# GSM_GPS.net
KiCad netlist of a schematic drawn in Altium Designer
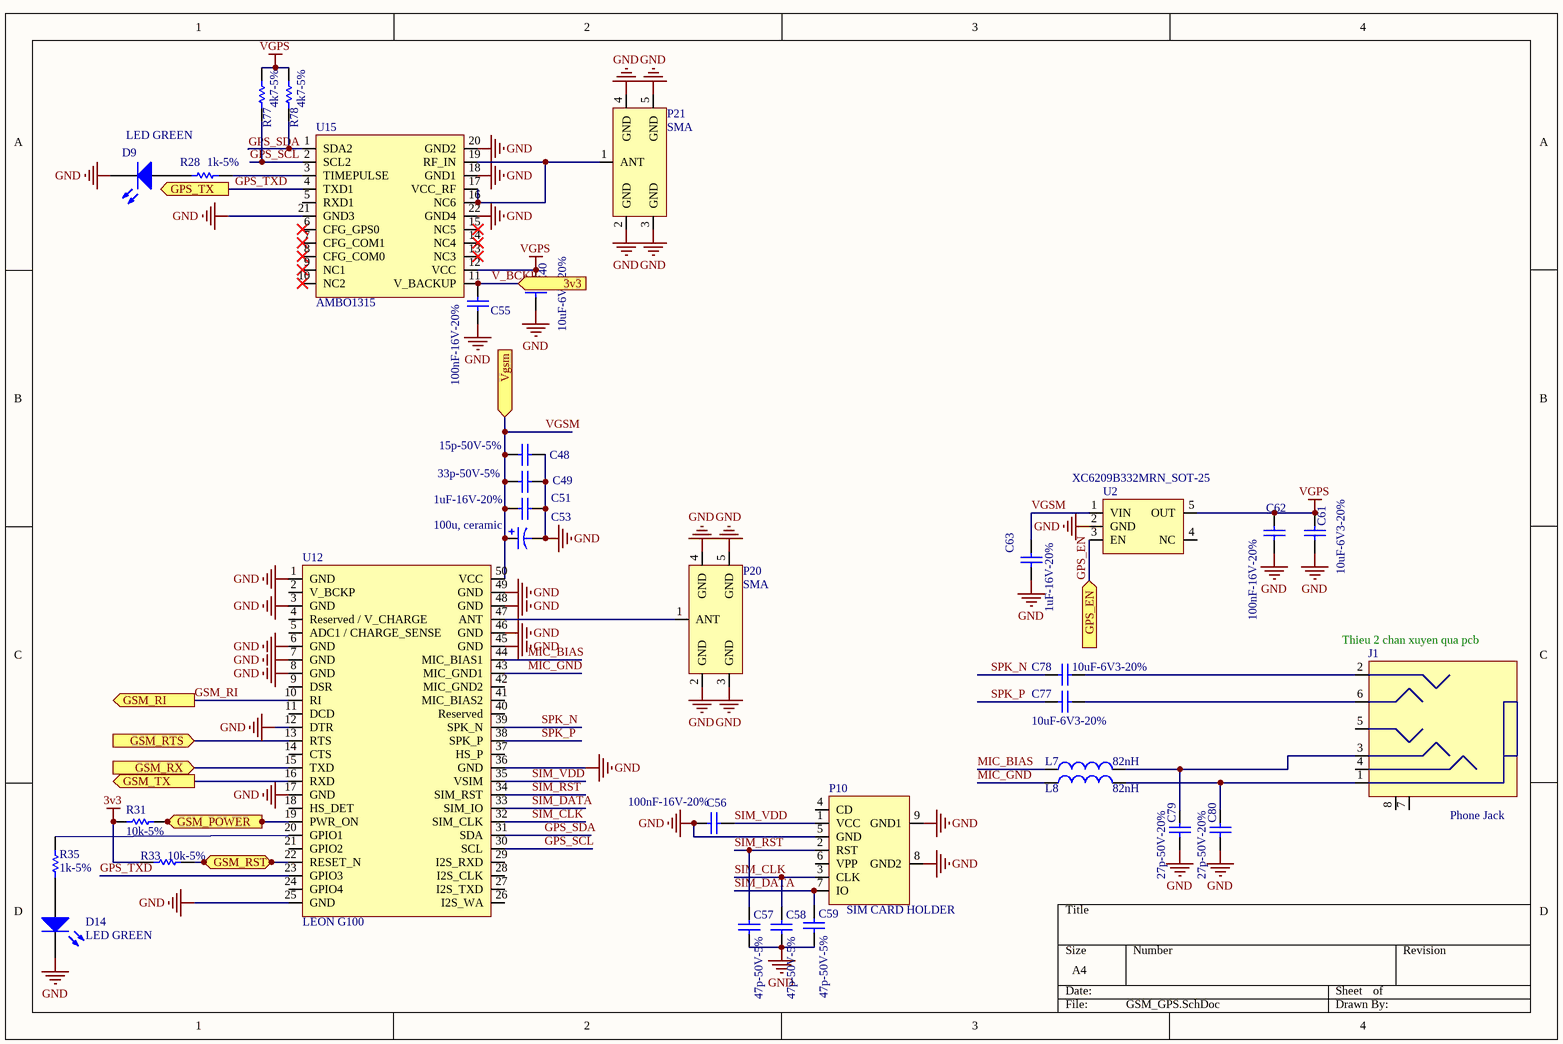
[diagram p0: GSM_GPS.SchDoc]

(export (version "E")
  (design (tool "Eeschema 10.0.6"))
  (components
    (comp (ref "C40")
      (value "10uF-6V3-20%")
      (footprint "C0603")
      (description "CAP CER 10UF 6.3V 20% X5R 0603")
      (fields
        (field (name "MANUFACTURER") "Murata Electronics North America")
        (field (name "DIGI-KEY PART NUMBER") "490-3896-1-ND")
        (field (name "PUBLISHER") "Altium Limited")
      )
      (libsource (lib "Miscellaneous Devices") (part "Cap"))
    )
    (comp (ref "C48")
      (value "15p-50V-5%")
      (footprint "C0402")
      (description "CAP CER 15PF 50V 5% NPO 0402")
      (fields
        (field (name "MANUFACTURER") "Yageo")
        (field (name "DIGI-KEY PART NUMBER") "311-1017-1-ND")
        (field (name "PUBLISHER") "Altium Limited")
      )
      (libsource (lib "Miscellaneous Devices") (part "Cap"))
    )
    (comp (ref "C49")
      (value "33p-50V-5%")
      (footprint "C0402")
      (description "CAP CER 33PF 50V 5% NPO 0402")
      (fields
        (field (name "MANUFACTURER") "Yageo")
        (field (name "DIGI-KEY PART NUMBER") "311-1020-1-ND")
        (field (name "PUBLISHER") "Altium Limited")
      )
      (libsource (lib "Miscellaneous Devices") (part "Cap"))
    )
    (comp (ref "C51")
      (value "1uF-16V-20%")
      (footprint "C0603")
      (description "CAP CER 1UF 16V Y5V 0603")
      (fields
        (field (name "MANUFACTURER") "Yageo")
        (field (name "DIGI-KEY PART NUMBER") "311-1372-1-ND")
        (field (name "PUBLISHER") "Altium Limited")
      )
      (libsource (lib "Miscellaneous Devices") (part "Cap"))
    )
    (comp (ref "C53")
      (value "100u, ceramic")
      (footprint "C1210")
      (description "CAP CER 100UF 10V 20% X5R 1812")
      (fields
        (field (name "DIGI-KEY PART NUMBER") "445-7743-2-ND")
        (field (name "MANUFACTURER PART NUMBER") "C4532X5R1A107M")
        (field (name "PUBLISHER") "Altium Limited")
      )
      (libsource (lib "Miscellaneous Devices") (part "Cap Pol3"))
    )
    (comp (ref "C55")
      (value "100nF-16V-20%")
      (footprint "C0402")
      (description "CAP CER 0.1UF 16V Y5V 0402")
      (fields
        (field (name "MANUFACTURER") "Yageo")
        (field (name "DIGI-KEY PART NUMBER") "311-1047-1-ND")
        (field (name "PUBLISHER") "Altium Limited")
      )
      (libsource (lib "Miscellaneous Devices") (part "Cap"))
    )
    (comp (ref "C56")
      (value "100nF-16V-20%")
      (footprint "C0402")
      (description "CAP CER 0.1UF 16V Y5V 0402")
      (fields
        (field (name "MANUFACTURER") "Yageo")
        (field (name "DIGI-KEY PART NUMBER") "311-1047-1-ND")
        (field (name "PUBLISHER") "Altium Limited")
      )
      (libsource (lib "Miscellaneous Devices") (part "Cap"))
    )
    (comp (ref "C57")
      (value "47p-50V-5%")
      (footprint "C0402")
      (description "CAP CER 47PF 50V 5% NPO 0402")
      (fields
        (field (name "MANUFACTURER") "Yageo")
        (field (name "DIGI-KEY PART NUMBER") "311-1021-1-ND")
        (field (name "PUBLISHER") "Altium Limited")
      )
      (libsource (lib "Miscellaneous Devices") (part "Cap"))
    )
    (comp (ref "C58")
      (value "47p-50V-5%")
      (footprint "C0402")
      (description "CAP CER 47PF 50V 5% NPO 0402")
      (fields
        (field (name "MANUFACTURER") "Yageo")
        (field (name "DIGI-KEY PART NUMBER") "311-1021-1-ND")
        (field (name "PUBLISHER") "Altium Limited")
      )
      (libsource (lib "Miscellaneous Devices") (part "Cap"))
    )
    (comp (ref "C59")
      (value "47p-50V-5%")
      (footprint "C0402")
      (description "CAP CER 47PF 50V 5% NPO 0402")
      (fields
        (field (name "MANUFACTURER") "Yageo")
        (field (name "DIGI-KEY PART NUMBER") "311-1021-1-ND")
        (field (name "PUBLISHER") "Altium Limited")
      )
      (libsource (lib "Miscellaneous Devices") (part "Cap"))
    )
    (comp (ref "C61")
      (value "10uF-6V3-20%")
      (footprint "C0603")
      (description "CAP CER 10UF 6.3V 20% X5R 0603")
      (fields
        (field (name "MANUFACTURER") "Murata Electronics North America")
        (field (name "DIGI-KEY PART NUMBER") "490-3896-1-ND")
        (field (name "PUBLISHER") "Altium Limited")
      )
      (libsource (lib "Miscellaneous Devices") (part "Cap"))
    )
    (comp (ref "C62")
      (value "100nF-16V-20%")
      (footprint "C0402")
      (description "CAP CER 0.1UF 16V Y5V 0402")
      (fields
        (field (name "MANUFACTURER") "Yageo")
        (field (name "DIGI-KEY PART NUMBER") "311-1047-1-ND")
        (field (name "PUBLISHER") "Altium Limited")
      )
      (libsource (lib "Miscellaneous Devices") (part "Cap"))
    )
    (comp (ref "C63")
      (value "1uF-16V-20%")
      (footprint "C0603")
      (description "CAP CER 1UF 16V Y5V 0603")
      (fields
        (field (name "MANUFACTURER") "Yageo")
        (field (name "DIGI-KEY PART NUMBER") "311-1372-1-ND")
        (field (name "PUBLISHER") "Altium Limited")
      )
      (libsource (lib "Miscellaneous Devices") (part "Cap"))
    )
    (comp (ref "C77")
      (value "10uF-6V3-20%")
      (footprint "C0603")
      (description "CAP CER 10UF 6.3V 20% X5R 0603")
      (fields
        (field (name "MANUFACTURER") "Murata Electronics North America")
        (field (name "DIGI-KEY PART NUMBER") "490-3896-1-ND")
        (field (name "PUBLISHER") "Altium Limited")
      )
      (libsource (lib "Miscellaneous Devices") (part "Cap"))
    )
    (comp (ref "C78")
      (value "10uF-6V3-20%")
      (footprint "C0603")
      (description "CAP CER 10UF 6.3V 20% X5R 0603")
      (fields
        (field (name "MANUFACTURER") "Murata Electronics North America")
        (field (name "DIGI-KEY PART NUMBER") "490-3896-1-ND")
        (field (name "PUBLISHER") "Altium Limited")
      )
      (libsource (lib "Miscellaneous Devices") (part "Cap"))
    )
    (comp (ref "C79")
      (value "27p-50V-20%")
      (footprint "C0402")
      (description "CAP CER 27PF 50V 5% NPO 0402")
      (fields
        (field (name "MANUFACTURER") "Murata Electronics North America")
        (field (name "DIGI-KEY PART NUMBER") "490-5869-1-ND")
        (field (name "PUBLISHER") "Altium Limited")
      )
      (libsource (lib "Miscellaneous Devices") (part "Cap"))
    )
    (comp (ref "C80")
      (value "27p-50V-20%")
      (footprint "C0402")
      (description "CAP CER 27PF 50V 5% NPO 0402")
      (fields
        (field (name "MANUFACTURER") "Murata Electronics North America")
        (field (name "DIGI-KEY PART NUMBER") "490-5869-1-ND")
        (field (name "PUBLISHER") "Altium Limited")
      )
      (libsource (lib "Miscellaneous Devices") (part "Cap"))
    )
    (comp (ref "D9")
      (value "LED GREEN")
      (footprint "LED0603-G")
      (description "LED GREEN CLEAR THIN 0603 SMD")
      (fields
        (field (name "DIGI-KEY PART NUMBER") "160-1446-2-ND")
        (field (name "MANUFACTURER") "Lite-On Inc")
        (field (name "PUBLISHER") "Altium Limited")
      )
      (libsource (lib "Miscellaneous Devices") (part "LED2"))
    )
    (comp (ref "D14")
      (value "LED GREEN")
      (footprint "LED0603-G")
      (description "LED GREEN CLEAR THIN 0603 SMD")
      (fields
        (field (name "DIGI-KEY PART NUMBER") "160-1446-2-ND")
        (field (name "MANUFACTURER") "Lite-On Inc")
        (field (name "PUBLISHER") "Altium Limited")
      )
      (libsource (lib "Miscellaneous Devices") (part "LED2"))
    )
    (comp (ref "J1")
      (value "Phone Jack")
      (footprint "PHONE JACK")
      (description "NA")
      (fields (field (name "MANUFACTURER") "tyrone"))
      (libsource (lib "Schlib1") (part "Phone Jack"))
    )
    (comp (ref "L7")
      (value "82nH")
      (footprint "R0402")
      (description "INDUCTOR 82NH 150MA 0402")
      (fields
        (field (name "DIGI-KEY PART NUMBER") "490-2634-1-ND")
        (field (name "MANUFACTURER PART NUMBER") "LQG15HS82NJ02D")
        (field (name "PUBLISHER") "Altium Limited")
      )
      (libsource (lib "Miscellaneous Devices") (part "Inductor"))
    )
    (comp (ref "L8")
      (value "82nH")
      (footprint "R0402")
      (description "INDUCTOR 82NH 150MA 0402")
      (fields
        (field (name "DIGI-KEY PART NUMBER") "490-2634-1-ND")
        (field (name "MANUFACTURER PART NUMBER") "LQG15HS82NJ02D")
        (field (name "PUBLISHER") "Altium Limited")
      )
      (libsource (lib "Miscellaneous Devices") (part "Inductor"))
    )
    (comp (ref "P10")
      (value "SIM CARD HOLDER")
      (footprint "SIM CARD HOLDER")
      (libsource (lib "Schlib1") (part "SIM CARD"))
    )
    (comp (ref "P20")
      (value "SMA")
      (footprint "ANTENA-SMA")
      (description "SMA-R/A-F")
      (libsource (lib "connector") (part "Component_1"))
    )
    (comp (ref "P21")
      (value "SMA")
      (footprint "ANTENA-SMA")
      (description "SMA-R/A-F")
      (libsource (lib "connector") (part "Component_1"))
    )
    (comp (ref "R28")
      (value "1k-5%")
      (footprint "R0402")
      (description "RES 1.0K OHM 1/16W 5% 0402 SMD")
      (fields
        (field (name "DIGI-KEY PART NUMBER") "311-1.0KJRCT-ND")
        (field (name "MANUFACTURER") "Yageo")
        (field (name "PUBLISHER") "Altium Limited")
      )
      (libsource (lib "Miscellaneous Devices") (part "Res1"))
    )
    (comp (ref "R31")
      (value "10k-5%")
      (footprint "R0402")
      (description "RES 10K OHM 1/16W 5% 0402 SMD")
      (fields
        (field (name "DIGI-KEY PART NUMBER") "311-10KJRCT-ND")
        (field (name "MANUFACTURER") "Yageo")
        (field (name "PUBLISHER") "Altium Limited")
      )
      (libsource (lib "Miscellaneous Devices") (part "Res1"))
    )
    (comp (ref "R33")
      (value "10k-5%")
      (footprint "R0402")
      (description "RES 10K OHM 1/16W 5% 0402 SMD")
      (fields
        (field (name "DIGI-KEY PART NUMBER") "311-10KJRCT-ND")
        (field (name "MANUFACTURER") "Yageo")
        (field (name "PUBLISHER") "Altium Limited")
      )
      (libsource (lib "Miscellaneous Devices") (part "Res1"))
    )
    (comp (ref "R35")
      (value "1k-5%")
      (footprint "R0402")
      (description "RES 1.0K OHM 1/16W 5% 0402 SMD")
      (fields
        (field (name "DIGI-KEY PART NUMBER") "311-1.0KJRCT-ND")
        (field (name "MANUFACTURER") "Yageo")
        (field (name "PUBLISHER") "Altium Limited")
      )
      (libsource (lib "Miscellaneous Devices") (part "Res1"))
    )
    (comp (ref "R77")
      (value "4k7-5%")
      (footprint "R0402")
      (description "RES 4.7K OHM 1/16W 5% 0402 SMD")
      (fields
        (field (name "DIGI-KEY PART NUMBER") "311-4.7KJRCT-ND")
        (field (name "MANUFACTURER") "Yageo")
        (field (name "PUBLISHER") "Altium Limited")
      )
      (libsource (lib "Miscellaneous Devices") (part "Res1"))
    )
    (comp (ref "R78")
      (value "4k7-5%")
      (footprint "R0402")
      (description "RES 4.7K OHM 1/16W 5% 0402 SMD")
      (fields
        (field (name "DIGI-KEY PART NUMBER") "311-4.7KJRCT-ND")
        (field (name "MANUFACTURER") "Yageo")
        (field (name "PUBLISHER") "Altium Limited")
      )
      (libsource (lib "Miscellaneous Devices") (part "Res1"))
    )
    (comp (ref "U2")
      (value "XC6209B332MRN_SOT-25")
      (footprint "SOT23-5")
      (fields (field (name "MANUFACTURER") "Tyrone"))
      (libsource (lib "Schlib1") (part "XC6209B332MRN_SOT-25"))
    )
    (comp (ref "U12")
      (value "LEON G100")
      (footprint "UBLOX")
      (fields (field (name "MANUFACTURER") "Tyrone"))
      (libsource (lib "gsm_module") (part "ublox"))
    )
    (comp (ref "U15")
      (value "AMBO1315")
      (footprint "GPS-module")
      (fields (field (name "MANUFACTURER") "Tyrone"))
      (libsource (lib "Schlib1") (part "UBLOX-GPS"))
    )
  )
  (nets
    (net (code "1") (name "/GPS_EN") (class "Default")
      (node (ref "U2") (pin "3") (pinfunction "EN_3") (pintype "passive"))
    )
    (net (code "2") (name "/GPS_SCL") (class "Default")
      (node (ref "R77") (pin "1") (pinfunction "1_1") (pintype "passive"))
      (node (ref "U12") (pin "30") (pinfunction "SCL_30") (pintype "passive"))
      (node (ref "U15") (pin "2") (pinfunction "SCL2_2") (pintype "passive"))
    )
    (net (code "3") (name "/GPS_SDA") (class "Default")
      (node (ref "R78") (pin "1") (pinfunction "1_1") (pintype "passive"))
      (node (ref "U12") (pin "31") (pinfunction "SDA_31") (pintype "passive"))
      (node (ref "U15") (pin "1") (pinfunction "SDA2_1") (pintype "passive"))
    )
    (net (code "4") (name "/GPS_TXD") (class "Default")
      (node (ref "U12") (pin "23") (pinfunction "GPIO3_23") (pintype "passive"))
      (node (ref "U15") (pin "4") (pinfunction "TXD1_4") (pintype "passive"))
    )
    (net (code "5") (name "/GSM_POWER") (class "Default")
      (node (ref "R31") (pin "2") (pinfunction "2_2") (pintype "passive"))
      (node (ref "U12") (pin "19") (pinfunction "PWR_ON_19") (pintype "passive"))
    )
    (net (code "6") (name "/GSM_RI") (class "Default")
      (node (ref "U12") (pin "10") (pinfunction "RI_10") (pintype "passive"))
    )
    (net (code "7") (name "/GSM_RST") (class "Default")
      (node (ref "R33") (pin "2") (pinfunction "2_2") (pintype "passive"))
      (node (ref "U12") (pin "22") (pinfunction "RESET_N_22") (pintype "passive"))
    )
    (net (code "8") (name "/GSM_RTS") (class "Default")
      (node (ref "U12") (pin "13") (pinfunction "RTS_13") (pintype "passive"))
    )
    (net (code "9") (name "/GSM_RX") (class "Default")
      (node (ref "U12") (pin "15") (pinfunction "TXD_15") (pintype "passive"))
    )
    (net (code "10") (name "/GSM_TX") (class "Default")
      (node (ref "U12") (pin "16") (pinfunction "RXD_16") (pintype "passive"))
    )
    (net (code "11") (name "/MIC_BIAS") (class "Default")
      (node (ref "L7") (pin "1") (pinfunction "1_1") (pintype "passive"))
      (node (ref "U12") (pin "44") (pinfunction "MIC_BIAS1_44") (pintype "passive"))
    )
    (net (code "12") (name "/MIC_GND") (class "Default")
      (node (ref "L8") (pin "1") (pinfunction "1_1") (pintype "passive"))
      (node (ref "U12") (pin "43") (pinfunction "MIC_GND1_43") (pintype "passive"))
    )
    (net (code "13") (name "/SIM_CLK") (class "Default")
      (node (ref "C58") (pin "2") (pinfunction "2_2") (pintype "passive"))
      (node (ref "P10") (pin "3") (pinfunction "CLK_3") (pintype "passive"))
      (node (ref "U12") (pin "32") (pinfunction "SIM_CLK_32") (pintype "passive"))
    )
    (net (code "14") (name "/SIM_DATA") (class "Default")
      (node (ref "C59") (pin "2") (pinfunction "2_2") (pintype "passive"))
      (node (ref "P10") (pin "7") (pinfunction "IO_7") (pintype "passive"))
      (node (ref "U12") (pin "33") (pinfunction "SIM_IO_33") (pintype "passive"))
    )
    (net (code "15") (name "/SIM_RST") (class "Default")
      (node (ref "C57") (pin "2") (pinfunction "2_2") (pintype "passive"))
      (node (ref "P10") (pin "2") (pinfunction "RST_2") (pintype "passive"))
      (node (ref "U12") (pin "34") (pinfunction "SIM_RST_34") (pintype "passive"))
    )
    (net (code "16") (name "/SIM_VDD") (class "Default")
      (node (ref "C56") (pin "1") (pinfunction "1_1") (pintype "passive"))
      (node (ref "P10") (pin "1") (pinfunction "VCC_1") (pintype "passive"))
      (node (ref "U12") (pin "35") (pinfunction "VSIM_35") (pintype "passive"))
    )
    (net (code "17") (name "/SPK_N") (class "Default")
      (node (ref "C78") (pin "2") (pinfunction "2_2") (pintype "passive"))
      (node (ref "U12") (pin "39") (pinfunction "SPK_N_39") (pintype "passive"))
    )
    (net (code "18") (name "/SPK_P") (class "Default")
      (node (ref "C77") (pin "2") (pinfunction "2_2") (pintype "passive"))
      (node (ref "U12") (pin "38") (pinfunction "SPK_P_38") (pintype "passive"))
    )
    (net (code "19") (name "/VGSM") (class "Default")
      (node (ref "C48") (pin "1") (pinfunction "1_1") (pintype "passive"))
      (node (ref "C49") (pin "1") (pinfunction "1_1") (pintype "passive"))
      (node (ref "C51") (pin "2") (pinfunction "2_2") (pintype "passive"))
      (node (ref "C53") (pin "1") (pinfunction "1_1") (pintype "passive"))
      (node (ref "C63") (pin "2") (pinfunction "2_2") (pintype "passive"))
      (node (ref "U12") (pin "50") (pinfunction "VCC_50") (pintype "passive"))
      (node (ref "U2") (pin "1") (pinfunction "VIN_1") (pintype "passive"))
    )
    (net (code "20") (name "3v3") (class "Default")
      (node (ref "C55") (pin "2") (pinfunction "2_2") (pintype "passive"))
      (node (ref "R31") (pin "1") (pinfunction "1_1") (pintype "passive"))
      (node (ref "R33") (pin "1") (pinfunction "1_1") (pintype "passive"))
      (node (ref "U15") (pin "11") (pinfunction "V_BACKUP_11") (pintype "passive"))
    )
    (net (code "21") (name "GND") (class "Default")
      (node (ref "C40") (pin "1") (pinfunction "1_1") (pintype "passive"))
      (node (ref "C48") (pin "2") (pinfunction "2_2") (pintype "passive"))
      (node (ref "C49") (pin "2") (pinfunction "2_2") (pintype "passive"))
      (node (ref "C51") (pin "1") (pinfunction "1_1") (pintype "passive"))
      (node (ref "C53") (pin "2") (pinfunction "2_2") (pintype "passive"))
      (node (ref "C55") (pin "1") (pinfunction "1_1") (pintype "passive"))
      (node (ref "C56") (pin "2") (pinfunction "2_2") (pintype "passive"))
      (node (ref "C57") (pin "1") (pinfunction "1_1") (pintype "passive"))
      (node (ref "C58") (pin "1") (pinfunction "1_1") (pintype "passive"))
      (node (ref "C59") (pin "1") (pinfunction "1_1") (pintype "passive"))
      (node (ref "C61") (pin "1") (pinfunction "1_1") (pintype "passive"))
      (node (ref "C62") (pin "1") (pinfunction "1_1") (pintype "passive"))
      (node (ref "C63") (pin "1") (pinfunction "1_1") (pintype "passive"))
      (node (ref "C79") (pin "2") (pinfunction "2_2") (pintype "passive"))
      (node (ref "C80") (pin "2") (pinfunction "2_2") (pintype "passive"))
      (node (ref "D14") (pin "2") (pinfunction "K_2") (pintype "passive"))
      (node (ref "D9") (pin "2") (pinfunction "K_2") (pintype "passive"))
      (node (ref "P10") (pin "5") (pinfunction "GND_5") (pintype "passive"))
      (node (ref "P10") (pin "8") (pinfunction "GND2_8") (pintype "passive"))
      (node (ref "P10") (pin "9") (pinfunction "GND1_9") (pintype "passive"))
      (node (ref "P20") (pin "2") (pinfunction "GND_2") (pintype "passive"))
      (node (ref "P20") (pin "3") (pinfunction "GND_3") (pintype "passive"))
      (node (ref "P20") (pin "4") (pinfunction "GND_4") (pintype "passive"))
      (node (ref "P20") (pin "5") (pinfunction "GND_5") (pintype "passive"))
      (node (ref "P21") (pin "2") (pinfunction "GND_2") (pintype "passive"))
      (node (ref "P21") (pin "3") (pinfunction "GND_3") (pintype "passive"))
      (node (ref "P21") (pin "4") (pinfunction "GND_4") (pintype "passive"))
      (node (ref "P21") (pin "5") (pinfunction "GND_5") (pintype "passive"))
      (node (ref "U12") (pin "1") (pinfunction "GND_1") (pintype "passive"))
      (node (ref "U12") (pin "12") (pinfunction "DTR_12") (pintype "passive"))
      (node (ref "U12") (pin "17") (pinfunction "GND_17") (pintype "passive"))
      (node (ref "U12") (pin "25") (pinfunction "GND_25") (pintype "passive"))
      (node (ref "U12") (pin "3") (pinfunction "GND_3") (pintype "passive"))
      (node (ref "U12") (pin "36") (pinfunction "GND_36") (pintype "passive"))
      (node (ref "U12") (pin "45") (pinfunction "GND_45") (pintype "passive"))
      (node (ref "U12") (pin "46") (pinfunction "GND_46") (pintype "passive"))
      (node (ref "U12") (pin "48") (pinfunction "GND_48") (pintype "passive"))
      (node (ref "U12") (pin "49") (pinfunction "GND_49") (pintype "passive"))
      (node (ref "U12") (pin "6") (pinfunction "GND_6") (pintype "passive"))
      (node (ref "U12") (pin "7") (pinfunction "GND_7") (pintype "passive"))
      (node (ref "U12") (pin "8") (pinfunction "GND_8") (pintype "passive"))
      (node (ref "U15") (pin "18") (pinfunction "GND1_18") (pintype "passive"))
      (node (ref "U15") (pin "20") (pinfunction "GND2_20") (pintype "passive"))
      (node (ref "U15") (pin "21") (pinfunction "GND3_21") (pintype "passive"))
      (node (ref "U15") (pin "22") (pinfunction "GND4_22") (pintype "passive"))
      (node (ref "U2") (pin "2") (pinfunction "GND_2") (pintype "passive"))
    )
    (net (code "22") (name "Net-(C77-Pad1)") (class "Default")
      (node (ref "C77") (pin "1") (pinfunction "1_1") (pintype "passive"))
      (node (ref "J1") (pin "6") (pinfunction "6_6") (pintype "passive"))
    )
    (net (code "23") (name "Net-(C78-Pad1)") (class "Default")
      (node (ref "C78") (pin "1") (pinfunction "1_1") (pintype "passive"))
      (node (ref "J1") (pin "2") (pinfunction "2_2") (pintype "passive"))
    )
    (net (code "24") (name "Net-(C79-Pad1)") (class "Default")
      (node (ref "C79") (pin "1") (pinfunction "1_1") (pintype "passive"))
      (node (ref "J1") (pin "3") (pinfunction "3_3") (pintype "passive"))
      (node (ref "L7") (pin "2") (pinfunction "2_2") (pintype "passive"))
    )
    (net (code "25") (name "Net-(C80-Pad1)") (class "Default")
      (node (ref "C80") (pin "1") (pinfunction "1_1") (pintype "passive"))
      (node (ref "J1") (pin "1") (pinfunction "1_1") (pintype "passive"))
      (node (ref "L8") (pin "2") (pinfunction "2_2") (pintype "passive"))
    )
    (net (code "26") (name "Net-(D9-A)") (class "Default")
      (node (ref "D9") (pin "1") (pinfunction "A_1") (pintype "passive"))
      (node (ref "R28") (pin "2") (pinfunction "2_2") (pintype "passive"))
    )
    (net (code "27") (name "Net-(D14-A)") (class "Default")
      (node (ref "D14") (pin "1") (pinfunction "A_1") (pintype "passive"))
      (node (ref "R35") (pin "1") (pinfunction "1_1") (pintype "passive"))
    )
    (net (code "28") (name "Net-(P20-ANT)") (class "Default")
      (node (ref "P20") (pin "1") (pinfunction "ANT_1") (pintype "passive"))
      (node (ref "U12") (pin "47") (pinfunction "ANT_47") (pintype "passive"))
    )
    (net (code "29") (name "Net-(P21-ANT)") (class "Default")
      (node (ref "P21") (pin "1") (pinfunction "ANT_1") (pintype "passive"))
      (node (ref "U15") (pin "16") (pinfunction "NC6_16") (pintype "passive"))
      (node (ref "U15") (pin "17") (pinfunction "VCC_RF_17") (pintype "passive"))
      (node (ref "U15") (pin "19") (pinfunction "RF_IN_19") (pintype "passive"))
    )
    (net (code "30") (name "Net-(U12-GPIO1)") (class "Default")
      (node (ref "R35") (pin "2") (pinfunction "2_2") (pintype "passive"))
      (node (ref "U12") (pin "20") (pinfunction "GPIO1_20") (pintype "passive"))
    )
    (net (code "31") (name "Net-(U15-TIMEPULSE)") (class "Default")
      (node (ref "R28") (pin "1") (pinfunction "1_1") (pintype "passive"))
      (node (ref "U15") (pin "3") (pinfunction "TIMEPULSE_3") (pintype "passive"))
    )
    (net (code "32") (name "VGPS") (class "Default")
      (node (ref "C40") (pin "2") (pinfunction "2_2") (pintype "passive"))
      (node (ref "C61") (pin "2") (pinfunction "2_2") (pintype "passive"))
      (node (ref "C62") (pin "2") (pinfunction "2_2") (pintype "passive"))
      (node (ref "R77") (pin "2") (pinfunction "2_2") (pintype "passive"))
      (node (ref "R78") (pin "2") (pinfunction "2_2") (pintype "passive"))
      (node (ref "U15") (pin "12") (pinfunction "VCC_12") (pintype "passive"))
      (node (ref "U2") (pin "5") (pinfunction "OUT_5") (pintype "passive"))
    )
    (net (code "33") (name "unconnected-(J1-Pad4)") (class "Default")
      (node (ref "J1") (pin "4") (pinfunction "4_4") (pintype "passive"))
    )
    (net (code "34") (name "unconnected-(J1-Pad5)") (class "Default")
      (node (ref "J1") (pin "5") (pinfunction "5_5") (pintype "passive"))
    )
    (net (code "35") (name "unconnected-(J1-Pad7)") (class "Default")
      (node (ref "J1") (pin "7") (pinfunction "7_7") (pintype "passive"))
    )
    (net (code "36") (name "unconnected-(J1-Pad8)") (class "Default")
      (node (ref "J1") (pin "8") (pinfunction "8_8") (pintype "passive"))
    )
    (net (code "37") (name "unconnected-(P10-CD-Pad4)") (class "Default")
      (node (ref "P10") (pin "4") (pinfunction "CD_4") (pintype "passive"))
    )
    (net (code "38") (name "unconnected-(P10-VPP-Pad6)") (class "Default")
      (node (ref "P10") (pin "6") (pinfunction "VPP_6") (pintype "passive"))
    )
    (net (code "39") (name "unconnected-(U2-NC-Pad4)") (class "Default")
      (node (ref "U2") (pin "4") (pinfunction "NC_4") (pintype "passive"))
    )
    (net (code "40") (name "unconnected-(U12-ADC1_{slash}_CHARGE_SENSE-Pad5)") (class "Default")
      (node (ref "U12") (pin "5") (pinfunction "ADC1_/_CHARGE_SENSE_5") (pintype "passive"))
    )
    (net (code "41") (name "unconnected-(U12-CTS-Pad14)") (class "Default")
      (node (ref "U12") (pin "14") (pinfunction "CTS_14") (pintype "passive"))
    )
    (net (code "42") (name "unconnected-(U12-DCD-Pad11)") (class "Default")
      (node (ref "U12") (pin "11") (pinfunction "DCD_11") (pintype "passive"))
    )
    (net (code "43") (name "unconnected-(U12-DSR-Pad9)") (class "Default")
      (node (ref "U12") (pin "9") (pinfunction "DSR_9") (pintype "passive"))
    )
    (net (code "44") (name "unconnected-(U12-GPIO2-Pad21)") (class "Default")
      (node (ref "U12") (pin "21") (pinfunction "GPIO2_21") (pintype "passive"))
    )
    (net (code "45") (name "unconnected-(U12-GPIO4-Pad24)") (class "Default")
      (node (ref "U12") (pin "24") (pinfunction "GPIO4_24") (pintype "passive"))
    )
    (net (code "46") (name "unconnected-(U12-HS_DET-Pad18)") (class "Default")
      (node (ref "U12") (pin "18") (pinfunction "HS_DET_18") (pintype "passive"))
    )
    (net (code "47") (name "unconnected-(U12-HS_P-Pad37)") (class "Default")
      (node (ref "U12") (pin "37") (pinfunction "HS_P_37") (pintype "passive"))
    )
    (net (code "48") (name "unconnected-(U12-I2S_CLK-Pad28)") (class "Default")
      (node (ref "U12") (pin "28") (pinfunction "I2S_CLK_28") (pintype "passive"))
    )
    (net (code "49") (name "unconnected-(U12-I2S_RXD-Pad29)") (class "Default")
      (node (ref "U12") (pin "29") (pinfunction "I2S_RXD_29") (pintype "passive"))
    )
    (net (code "50") (name "unconnected-(U12-I2S_TXD-Pad27)") (class "Default")
      (node (ref "U12") (pin "27") (pinfunction "I2S_TXD_27") (pintype "passive"))
    )
    (net (code "51") (name "unconnected-(U12-I2S_WA-Pad26)") (class "Default")
      (node (ref "U12") (pin "26") (pinfunction "I2S_WA_26") (pintype "passive"))
    )
    (net (code "52") (name "unconnected-(U12-MIC_BIAS2-Pad41)") (class "Default")
      (node (ref "U12") (pin "41") (pinfunction "MIC_BIAS2_41") (pintype "passive"))
    )
    (net (code "53") (name "unconnected-(U12-MIC_GND2-Pad42)") (class "Default")
      (node (ref "U12") (pin "42") (pinfunction "MIC_GND2_42") (pintype "passive"))
    )
    (net (code "54") (name "unconnected-(U12-Reserved-Pad40)") (class "Default")
      (node (ref "U12") (pin "40") (pinfunction "Reserved_40") (pintype "passive"))
    )
    (net (code "55") (name "unconnected-(U12-Reserved_{slash}_V_CHARGE-Pad4)") (class "Default")
      (node (ref "U12") (pin "4") (pinfunction "Reserved_/_V_CHARGE_4") (pintype "passive"))
    )
    (net (code "56") (name "unconnected-(U12-V_BCKP-Pad2)") (class "Default")
      (node (ref "U12") (pin "2") (pinfunction "V_BCKP_2") (pintype "passive"))
    )
    (net (code "57") (name "unconnected-(U15-CFG_COM0-Pad8)") (class "Default")
      (node (ref "U15") (pin "8") (pinfunction "CFG_COM0_8") (pintype "passive+no_connect"))
    )
    (net (code "58") (name "unconnected-(U15-CFG_COM1-Pad7)") (class "Default")
      (node (ref "U15") (pin "7") (pinfunction "CFG_COM1_7") (pintype "passive+no_connect"))
    )
    (net (code "59") (name "unconnected-(U15-CFG_GPS0-Pad6)") (class "Default")
      (node (ref "U15") (pin "6") (pinfunction "CFG_GPS0_6") (pintype "passive+no_connect"))
    )
    (net (code "60") (name "unconnected-(U15-NC1-Pad9)") (class "Default")
      (node (ref "U15") (pin "9") (pinfunction "NC1_9") (pintype "passive+no_connect"))
    )
    (net (code "61") (name "unconnected-(U15-NC2-Pad10)") (class "Default")
      (node (ref "U15") (pin "10") (pinfunction "NC2_10") (pintype "passive+no_connect"))
    )
    (net (code "62") (name "unconnected-(U15-NC3-Pad13)") (class "Default")
      (node (ref "U15") (pin "13") (pinfunction "NC3_13") (pintype "passive+no_connect"))
    )
    (net (code "63") (name "unconnected-(U15-NC4-Pad14)") (class "Default")
      (node (ref "U15") (pin "14") (pinfunction "NC4_14") (pintype "passive+no_connect"))
    )
    (net (code "64") (name "unconnected-(U15-NC5-Pad15)") (class "Default")
      (node (ref "U15") (pin "15") (pinfunction "NC5_15") (pintype "passive+no_connect"))
    )
    (net (code "65") (name "unconnected-(U15-RXD1-Pad5)") (class "Default")
      (node (ref "U15") (pin "5") (pinfunction "RXD1_5") (pintype "passive"))
    )
  )
)
